# Carolo_31012020.net
KiCad netlist of a schematic drawn in EAGLE
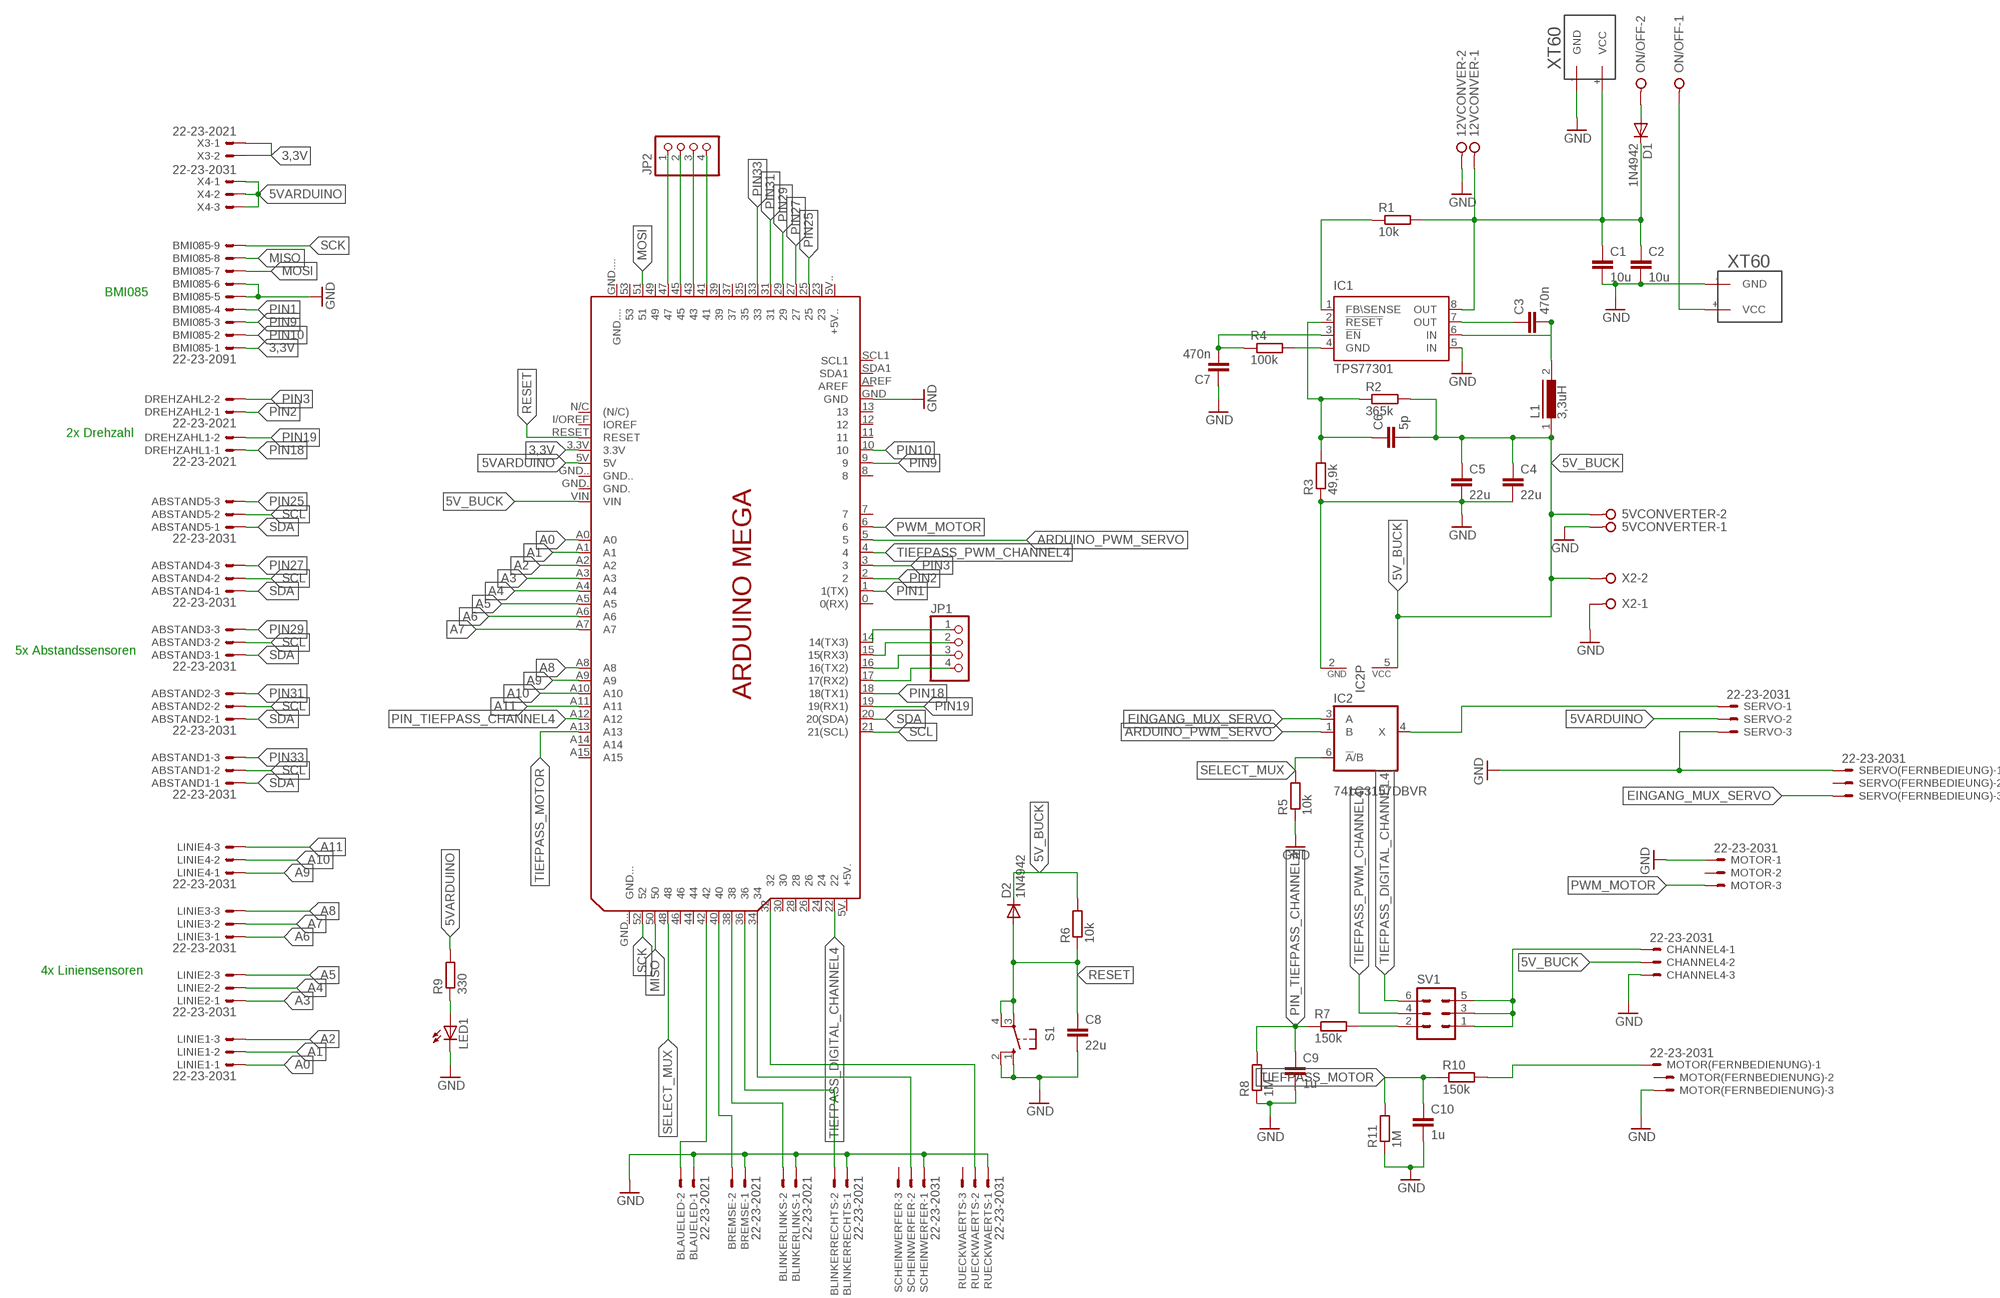
[diagram p0: schematic, sheet 1]

(export (version "E")
  (design (tool "Eeschema 10.0.6"))
  (components
    (comp (ref "5VCONVERTER")
      (value "W237-02P")
      (footprint "eagle-import:W237-132")
      (libsource (lib "eagle-import") (part "W237-02P"))
    )
    (comp (ref "12VCONVER")
      (value "W237-02P")
      (footprint "eagle-import:W237-132")
      (libsource (lib "eagle-import") (part "W237-02P"))
    )
    (comp (ref "ABSTAND1")
      (value "22-23-2031")
      (footprint "eagle-import:22-23-2031")
      (fields (field (name "MF") "MOLEX"))
      (libsource (lib "eagle-import") (part "22-23-2031"))
    )
    (comp (ref "ABSTAND2")
      (value "22-23-2031")
      (footprint "eagle-import:22-23-2031")
      (fields (field (name "MF") "MOLEX"))
      (libsource (lib "eagle-import") (part "22-23-2031"))
    )
    (comp (ref "ABSTAND3")
      (value "22-23-2031")
      (footprint "eagle-import:22-23-2031")
      (fields (field (name "MF") "MOLEX"))
      (libsource (lib "eagle-import") (part "22-23-2031"))
    )
    (comp (ref "ABSTAND4")
      (value "22-23-2031")
      (footprint "eagle-import:22-23-2031")
      (fields (field (name "MF") "MOLEX"))
      (libsource (lib "eagle-import") (part "22-23-2031"))
    )
    (comp (ref "ABSTAND5")
      (value "22-23-2031")
      (footprint "eagle-import:22-23-2031")
      (fields (field (name "MF") "MOLEX"))
      (libsource (lib "eagle-import") (part "22-23-2031"))
    )
    (comp (ref "BLAUELED")
      (value "22-23-2021")
      (footprint "eagle-import:22-23-2021")
      (fields (field (name "MF") "MOLEX"))
      (libsource (lib "eagle-import") (part "22-23-2021"))
    )
    (comp (ref "BLINKERLINKS")
      (value "22-23-2021")
      (footprint "eagle-import:22-23-2021")
      (fields (field (name "MF") "MOLEX"))
      (libsource (lib "eagle-import") (part "22-23-2021"))
    )
    (comp (ref "BLINKERRECHTS")
      (value "22-23-2021")
      (footprint "eagle-import:22-23-2021")
      (fields (field (name "MF") "MOLEX"))
      (libsource (lib "eagle-import") (part "22-23-2021"))
    )
    (comp (ref "BMI085")
      (value "22-23-2091")
      (footprint "eagle-import:22-23-2091")
      (fields (field (name "MF") "MOLEX"))
      (libsource (lib "eagle-import") (part "22-23-2091"))
    )
    (comp (ref "BREMSE")
      (value "22-23-2021")
      (footprint "eagle-import:22-23-2021")
      (fields (field (name "MF") "MOLEX"))
      (libsource (lib "eagle-import") (part "22-23-2021"))
    )
    (comp (ref "C1")
      (value "10u")
      (footprint "eagle-import:C2.5-3")
      (libsource (lib "eagle-import") (part "C2,5-3"))
    )
    (comp (ref "C2")
      (value "10u")
      (footprint "eagle-import:C2.5-3")
      (libsource (lib "eagle-import") (part "C2,5-3"))
    )
    (comp (ref "C3")
      (value "470n")
      (footprint "eagle-import:C2.5-3")
      (libsource (lib "eagle-import") (part "C2,5-3"))
    )
    (comp (ref "C4")
      (value "22u")
      (footprint "eagle-import:C2.5-3")
      (libsource (lib "eagle-import") (part "C2,5-3"))
    )
    (comp (ref "C5")
      (value "22u")
      (footprint "eagle-import:C2.5-3")
      (libsource (lib "eagle-import") (part "C2,5-3"))
    )
    (comp (ref "C6")
      (value "5p")
      (footprint "eagle-import:C2.5-3")
      (libsource (lib "eagle-import") (part "C2,5-3"))
    )
    (comp (ref "C7")
      (value "470n")
      (footprint "eagle-import:C2.5-3")
      (libsource (lib "eagle-import") (part "C2,5-3"))
    )
    (comp (ref "C8")
      (value "22u")
      (footprint "eagle-import:C2.5-3")
      (libsource (lib "eagle-import") (part "C2,5-3"))
    )
    (comp (ref "C9")
      (value "1u")
      (footprint "eagle-import:C2.5-3")
      (libsource (lib "eagle-import") (part "C2,5-3"))
    )
    (comp (ref "C10")
      (value "1u")
      (footprint "eagle-import:C2.5-3")
      (libsource (lib "eagle-import") (part "C2,5-3"))
    )
    (comp (ref "CHANNEL4")
      (value "22-23-2031")
      (footprint "eagle-import:22-23-2031")
      (fields (field (name "MF") "MOLEX"))
      (libsource (lib "eagle-import") (part "22-23-2031"))
    )
    (comp (ref "D1")
      (value "1N4942")
      (footprint "eagle-import:DO41-10")
      (libsource (lib "eagle-import") (part "1N4942"))
    )
    (comp (ref "D2")
      (value "1N4942")
      (footprint "eagle-import:DO41-10")
      (libsource (lib "eagle-import") (part "1N4942"))
    )
    (comp (ref "DREHZAHL1")
      (value "22-23-2021")
      (footprint "eagle-import:22-23-2021")
      (fields (field (name "MF") "MOLEX"))
      (libsource (lib "eagle-import") (part "22-23-2021"))
    )
    (comp (ref "DREHZAHL2")
      (value "22-23-2021")
      (footprint "eagle-import:22-23-2021")
      (fields (field (name "MF") "MOLEX"))
      (libsource (lib "eagle-import") (part "22-23-2021"))
    )
    (comp (ref "IC1")
      (value "TPS77301")
      (footprint "eagle-import:SOP-08")
      (fields (field (name "MF") "TEXAS INSTRUMENT CONNECTORS") (field (name "MPN") "TPS77301DGK"))
      (libsource (lib "eagle-import") (part "TPS77301"))
    )
    (comp (ref "IC2")
      (value "741G3157DBVR")
      (footprint "eagle-import:DBV_R-PDSO-G6")
      (libsource (lib "eagle-import") (part "741G3157DBVR"))
    )
    (comp (ref "JP1")
      (value "PINHD-1X4")
      (footprint "eagle-import:1X04")
      (libsource (lib "eagle-import") (part "PINHD-1X4"))
    )
    (comp (ref "JP2")
      (value "PINHD-1X4")
      (footprint "eagle-import:1X04")
      (libsource (lib "eagle-import") (part "PINHD-1X4"))
    )
    (comp (ref "L1")
      (value "3,3uH")
      (footprint "eagle-import:82114R")
      (libsource (lib "eagle-import") (part "82114R"))
    )
    (comp (ref "LED1")
      (value "LED5MM")
      (footprint "eagle-import:LED5MM")
      (libsource (lib "eagle-import") (part "LED5MM"))
    )
    (comp (ref "LINIE1")
      (value "22-23-2031")
      (footprint "eagle-import:22-23-2031")
      (fields (field (name "MF") "MOLEX"))
      (libsource (lib "eagle-import") (part "22-23-2031"))
    )
    (comp (ref "LINIE2")
      (value "22-23-2031")
      (footprint "eagle-import:22-23-2031")
      (fields (field (name "MF") "MOLEX"))
      (libsource (lib "eagle-import") (part "22-23-2031"))
    )
    (comp (ref "LINIE3")
      (value "22-23-2031")
      (footprint "eagle-import:22-23-2031")
      (fields (field (name "MF") "MOLEX"))
      (libsource (lib "eagle-import") (part "22-23-2031"))
    )
    (comp (ref "LINIE4")
      (value "22-23-2031")
      (footprint "eagle-import:22-23-2031")
      (fields (field (name "MF") "MOLEX"))
      (libsource (lib "eagle-import") (part "22-23-2031"))
    )
    (comp (ref "MOTOR")
      (value "22-23-2031")
      (footprint "eagle-import:22-23-2031")
      (fields (field (name "MF") "MOLEX"))
      (libsource (lib "eagle-import") (part "22-23-2031"))
    )
    (comp (ref "MOTOR(FERNBEDIENUNG)")
      (value "22-23-2031")
      (footprint "eagle-import:22-23-2031")
      (fields (field (name "MF") "MOLEX"))
      (libsource (lib "eagle-import") (part "22-23-2031"))
    )
    (comp (ref "ON/OFF")
      (value "W237-02P")
      (footprint "eagle-import:W237-132")
      (libsource (lib "eagle-import") (part "W237-02P"))
    )
    (comp (ref "PCB1")
      (value "ARDUINO_MEGA")
      (footprint "eagle-import:ARDUINO_MEGA")
      (libsource (lib "eagle-import") (part "ARDUINO_MEGA"))
    )
    (comp (ref "R1")
      (value "10k")
      (footprint "eagle-import:0411_15")
      (libsource (lib "eagle-import") (part "R-EU_0411/15"))
    )
    (comp (ref "R2")
      (value "365k")
      (footprint "eagle-import:0411_15")
      (libsource (lib "eagle-import") (part "R-EU_0411/15"))
    )
    (comp (ref "R3")
      (value "49,9k")
      (footprint "eagle-import:0411_15")
      (libsource (lib "eagle-import") (part "R-EU_0411/15"))
    )
    (comp (ref "R4")
      (value "100k")
      (footprint "eagle-import:0411_15")
      (libsource (lib "eagle-import") (part "R-EU_0411/15"))
    )
    (comp (ref "R5")
      (value "10k")
      (footprint "eagle-import:0411_15")
      (libsource (lib "eagle-import") (part "R-EU_0411/15"))
    )
    (comp (ref "R6")
      (value "10k")
      (footprint "eagle-import:0411_15")
      (libsource (lib "eagle-import") (part "R-EU_0411/15"))
    )
    (comp (ref "R7")
      (value "150k")
      (footprint "eagle-import:0411_15")
      (libsource (lib "eagle-import") (part "R-EU_0411/15"))
    )
    (comp (ref "R8")
      (value "1M")
      (footprint "eagle-import:0411_15")
      (libsource (lib "eagle-import") (part "R-EU_0411/15"))
    )
    (comp (ref "R9")
      (value "330")
      (footprint "eagle-import:0411_15")
      (libsource (lib "eagle-import") (part "R-EU_0411/15"))
    )
    (comp (ref "R10")
      (value "150k")
      (footprint "eagle-import:0411_15")
      (libsource (lib "eagle-import") (part "R-EU_0411/15"))
    )
    (comp (ref "R11")
      (value "1M")
      (footprint "eagle-import:0411_15")
      (libsource (lib "eagle-import") (part "R-EU_0411/15"))
    )
    (comp (ref "RUECKWAERTS")
      (value "22-23-2031")
      (footprint "eagle-import:22-23-2031")
      (fields (field (name "MF") "MOLEX"))
      (libsource (lib "eagle-import") (part "22-23-2031"))
    )
    (comp (ref "S1")
      (value "10-XX")
      (footprint "eagle-import:B3F-10XX")
      (fields (field (name "MPN") "B3F-1000"))
      (libsource (lib "eagle-import") (part "10-XX"))
    )
    (comp (ref "SCHEINWERFER")
      (value "22-23-2031")
      (footprint "eagle-import:22-23-2031")
      (fields (field (name "MF") "MOLEX"))
      (libsource (lib "eagle-import") (part "22-23-2031"))
    )
    (comp (ref "SERVO")
      (value "22-23-2031")
      (footprint "eagle-import:22-23-2031")
      (fields (field (name "MF") "MOLEX"))
      (libsource (lib "eagle-import") (part "22-23-2031"))
    )
    (comp (ref "SERVO(FERNBEDIEUNG)")
      (value "22-23-2031")
      (footprint "eagle-import:22-23-2031")
      (fields (field (name "MF") "MOLEX"))
      (libsource (lib "eagle-import") (part "22-23-2031"))
    )
    (comp (ref "SV1")
      (value "ML6")
      (footprint "eagle-import:ML6")
      (libsource (lib "eagle-import") (part "ML6"))
    )
    (comp (ref "U$1")
      (value "XT60")
      (footprint "eagle-import:XT60")
      (libsource (lib "eagle-import") (part "XT60"))
    )
    (comp (ref "U$2")
      (value "XT60")
      (footprint "eagle-import:XT60")
      (libsource (lib "eagle-import") (part "XT60"))
    )
    (comp (ref "X2")
      (value "W237-02P")
      (footprint "eagle-import:W237-132")
      (libsource (lib "eagle-import") (part "W237-02P"))
    )
    (comp (ref "X3")
      (value "22-23-2021")
      (footprint "eagle-import:22-23-2021")
      (fields (field (name "MF") "MOLEX"))
      (libsource (lib "eagle-import") (part "22-23-2021"))
    )
    (comp (ref "X4")
      (value "22-23-2031")
      (footprint "eagle-import:22-23-2031")
      (fields (field (name "MF") "MOLEX"))
      (libsource (lib "eagle-import") (part "22-23-2031"))
    )
  )
  (nets
    (net (code "1") (name "3,3V") (class "Default")
      (node (ref "BMI085") (pin "1") (pinfunction "S_1") (pintype "passive"))
      (node (ref "PCB1") (pin "3.3V") (pinfunction "3.3V_3.3V") (pintype "bidirectional"))
      (node (ref "X3") (pin "1") (pinfunction "S_1") (pintype "passive"))
      (node (ref "X3") (pin "2") (pinfunction "S_2") (pintype "passive"))
    )
    (net (code "2") (name "5VARDUINO") (class "Default")
      (node (ref "PCB1") (pin "5V") (pinfunction "5V_5V") (pintype "bidirectional"))
      (node (ref "R9") (pin "2") (pinfunction "2_2") (pintype "passive"))
      (node (ref "SERVO") (pin "2") (pinfunction "S_2") (pintype "passive"))
      (node (ref "X4") (pin "1") (pinfunction "S_1") (pintype "passive"))
      (node (ref "X4") (pin "2") (pinfunction "S_2") (pintype "passive"))
      (node (ref "X4") (pin "3") (pinfunction "S_3") (pintype "passive"))
    )
    (net (code "3") (name "5V_BUCK") (class "Default")
      (node (ref "5VCONVERTER") (pin "2") (pinfunction "KL_2") (pintype "passive"))
      (node (ref "C4") (pin "1") (pinfunction "1_1") (pintype "passive"))
      (node (ref "C5") (pin "1") (pinfunction "1_1") (pintype "passive"))
      (node (ref "C6") (pin "2") (pinfunction "2_2") (pintype "passive"))
      (node (ref "CHANNEL4") (pin "2") (pinfunction "S_2") (pintype "passive"))
      (node (ref "D2") (pin "C") (pinfunction "C_C") (pintype "passive"))
      (node (ref "IC2") (pin "5") (pinfunction "VCC_5") (pintype "power_in"))
      (node (ref "L1") (pin "1") (pinfunction "1_1") (pintype "passive"))
      (node (ref "PCB1") (pin "VIN") (pinfunction "VIN_VIN") (pintype "bidirectional"))
      (node (ref "R2") (pin "2") (pinfunction "2_2") (pintype "passive"))
      (node (ref "R6") (pin "2") (pinfunction "2_2") (pintype "passive"))
      (node (ref "X2") (pin "2") (pinfunction "KL_2") (pintype "passive"))
    )
    (net (code "4") (name "A0") (class "Default")
      (node (ref "LINIE1") (pin "1") (pinfunction "S_1") (pintype "passive"))
      (node (ref "PCB1") (pin "A0") (pinfunction "A0_A0") (pintype "bidirectional"))
    )
    (net (code "5") (name "A1") (class "Default")
      (node (ref "LINIE1") (pin "2") (pinfunction "S_2") (pintype "passive"))
      (node (ref "PCB1") (pin "A1") (pinfunction "A1_A1") (pintype "bidirectional"))
    )
    (net (code "6") (name "A2") (class "Default")
      (node (ref "LINIE1") (pin "3") (pinfunction "S_3") (pintype "passive"))
      (node (ref "PCB1") (pin "A2") (pinfunction "A2_A2") (pintype "bidirectional"))
    )
    (net (code "7") (name "A3") (class "Default")
      (node (ref "LINIE2") (pin "1") (pinfunction "S_1") (pintype "passive"))
      (node (ref "PCB1") (pin "A3") (pinfunction "A3_A3") (pintype "bidirectional"))
    )
    (net (code "8") (name "A4") (class "Default")
      (node (ref "LINIE2") (pin "2") (pinfunction "S_2") (pintype "passive"))
      (node (ref "PCB1") (pin "A4") (pinfunction "A4_A4") (pintype "bidirectional"))
    )
    (net (code "9") (name "A5") (class "Default")
      (node (ref "LINIE2") (pin "3") (pinfunction "S_3") (pintype "passive"))
      (node (ref "PCB1") (pin "A5") (pinfunction "A5_A5") (pintype "bidirectional"))
    )
    (net (code "10") (name "A6") (class "Default")
      (node (ref "LINIE3") (pin "1") (pinfunction "S_1") (pintype "passive"))
      (node (ref "PCB1") (pin "A6") (pinfunction "A6_A6") (pintype "bidirectional"))
    )
    (net (code "11") (name "A7") (class "Default")
      (node (ref "LINIE3") (pin "2") (pinfunction "S_2") (pintype "passive"))
      (node (ref "PCB1") (pin "A7") (pinfunction "A7_A7") (pintype "bidirectional"))
    )
    (net (code "12") (name "A8") (class "Default")
      (node (ref "LINIE3") (pin "3") (pinfunction "S_3") (pintype "passive"))
      (node (ref "PCB1") (pin "A8") (pinfunction "A8_A8") (pintype "bidirectional"))
    )
    (net (code "13") (name "A9") (class "Default")
      (node (ref "LINIE4") (pin "1") (pinfunction "S_1") (pintype "passive"))
      (node (ref "PCB1") (pin "A9") (pinfunction "A9_A9") (pintype "bidirectional"))
    )
    (net (code "14") (name "A10") (class "Default")
      (node (ref "LINIE4") (pin "2") (pinfunction "S_2") (pintype "passive"))
      (node (ref "PCB1") (pin "A10") (pinfunction "A10_A10") (pintype "bidirectional"))
    )
    (net (code "15") (name "A11") (class "Default")
      (node (ref "LINIE4") (pin "3") (pinfunction "S_3") (pintype "passive"))
      (node (ref "PCB1") (pin "A11") (pinfunction "A11_A11") (pintype "bidirectional"))
    )
    (net (code "16") (name "ARDUINO_PWM_SERVO") (class "Default")
      (node (ref "IC2") (pin "1") (pinfunction "B_1") (pintype "bidirectional"))
      (node (ref "PCB1") (pin "5") (pinfunction "5_5") (pintype "bidirectional"))
    )
    (net (code "17") (name "EINGANG_MUX_SERVO") (class "Default")
      (node (ref "IC2") (pin "3") (pinfunction "A_3") (pintype "bidirectional"))
      (node (ref "SERVO(FERNBEDIEUNG)") (pin "3") (pinfunction "S_3") (pintype "passive"))
    )
    (net (code "18") (name "GND") (class "Default")
      (node (ref "12VCONVER") (pin "2") (pinfunction "KL_2") (pintype "passive"))
      (node (ref "5VCONVERTER") (pin "1") (pinfunction "KL_1") (pintype "passive"))
      (node (ref "BLAUELED") (pin "1") (pinfunction "S_1") (pintype "passive"))
      (node (ref "BLINKERLINKS") (pin "1") (pinfunction "S_1") (pintype "passive"))
      (node (ref "BLINKERRECHTS") (pin "1") (pinfunction "S_1") (pintype "passive"))
      (node (ref "BMI085") (pin "5") (pinfunction "S_5") (pintype "passive"))
      (node (ref "BMI085") (pin "6") (pinfunction "S_6") (pintype "passive"))
      (node (ref "BREMSE") (pin "1") (pinfunction "S_1") (pintype "passive"))
      (node (ref "C1") (pin "2") (pinfunction "2_2") (pintype "passive"))
      (node (ref "C10") (pin "2") (pinfunction "2_2") (pintype "passive"))
      (node (ref "C2") (pin "2") (pinfunction "2_2") (pintype "passive"))
      (node (ref "C4") (pin "2") (pinfunction "2_2") (pintype "passive"))
      (node (ref "C5") (pin "2") (pinfunction "2_2") (pintype "passive"))
      (node (ref "C7") (pin "1") (pinfunction "1_1") (pintype "passive"))
      (node (ref "C8") (pin "2") (pinfunction "2_2") (pintype "passive"))
      (node (ref "C9") (pin "2") (pinfunction "2_2") (pintype "passive"))
      (node (ref "CHANNEL4") (pin "3") (pinfunction "S_3") (pintype "passive"))
      (node (ref "IC1") (pin "5") (pinfunction "IN_5") (pintype "input"))
      (node (ref "IC2") (pin "2") (pinfunction "GND_2") (pintype "power_in"))
      (node (ref "LED1") (pin "K") (pinfunction "C_K") (pintype "passive"))
      (node (ref "MOTOR") (pin "1") (pinfunction "S_1") (pintype "passive"))
      (node (ref "MOTOR(FERNBEDIENUNG)") (pin "3") (pinfunction "S_3") (pintype "passive"))
      (node (ref "PCB1") (pin "GND") (pinfunction "GND_GND") (pintype "bidirectional"))
      (node (ref "R11") (pin "1") (pinfunction "1_1") (pintype "passive"))
      (node (ref "R3") (pin "1") (pinfunction "1_1") (pintype "passive"))
      (node (ref "R5") (pin "1") (pinfunction "1_1") (pintype "passive"))
      (node (ref "R8") (pin "1") (pinfunction "1_1") (pintype "passive"))
      (node (ref "RUECKWAERTS") (pin "1") (pinfunction "S_1") (pintype "passive"))
      (node (ref "S1") (pin "1") (pinfunction "S_1") (pintype "passive"))
      (node (ref "S1") (pin "2") (pinfunction "S1_2") (pintype "passive"))
      (node (ref "SCHEINWERFER") (pin "1") (pinfunction "S_1") (pintype "passive"))
      (node (ref "SERVO") (pin "3") (pinfunction "S_3") (pintype "passive"))
      (node (ref "SERVO(FERNBEDIEUNG)") (pin "1") (pinfunction "S_1") (pintype "passive"))
      (node (ref "U$1") (pin "-") (pinfunction "GND_-") (pintype "bidirectional"))
      (node (ref "U$2") (pin "-") (pinfunction "GND_-") (pintype "bidirectional"))
      (node (ref "X2") (pin "1") (pinfunction "KL_1") (pintype "passive"))
    )
    (net (code "19") (name "MISO") (class "Default")
      (node (ref "BMI085") (pin "8") (pinfunction "S_8") (pintype "passive"))
      (node (ref "PCB1") (pin "50") (pinfunction "50_50") (pintype "bidirectional"))
    )
    (net (code "20") (name "MOSI") (class "Default")
      (node (ref "BMI085") (pin "7") (pinfunction "S_7") (pintype "passive"))
      (node (ref "PCB1") (pin "51") (pinfunction "51_51") (pintype "bidirectional"))
    )
    (net (code "21") (name "Net-(12VCONVERA-KL)") (class "Default")
      (node (ref "12VCONVER") (pin "1") (pinfunction "KL_1") (pintype "passive"))
      (node (ref "C1") (pin "1") (pinfunction "1_1") (pintype "passive"))
      (node (ref "C2") (pin "1") (pinfunction "1_1") (pintype "passive"))
      (node (ref "D1") (pin "C") (pinfunction "C_C") (pintype "passive"))
      (node (ref "IC1") (pin "8") (pinfunction "OUT_8") (pintype "passive"))
      (node (ref "R1") (pin "2") (pinfunction "2_2") (pintype "passive"))
      (node (ref "U$2") (pin "+") (pinfunction "VCC_+") (pintype "bidirectional"))
    )
    (net (code "22") (name "Net-(BLAUELEDB-S)") (class "Default")
      (node (ref "BLAUELED") (pin "2") (pinfunction "S_2") (pintype "passive"))
      (node (ref "PCB1") (pin "42") (pinfunction "42_42") (pintype "bidirectional"))
    )
    (net (code "23") (name "Net-(BLINKERLINKSB-S)") (class "Default")
      (node (ref "BLINKERLINKS") (pin "2") (pinfunction "S_2") (pintype "passive"))
      (node (ref "PCB1") (pin "38") (pinfunction "38_38") (pintype "bidirectional"))
    )
    (net (code "24") (name "Net-(BLINKERRECHTSB-S)") (class "Default")
      (node (ref "BLINKERRECHTS") (pin "2") (pinfunction "S_2") (pintype "passive"))
      (node (ref "PCB1") (pin "36") (pinfunction "36_36") (pintype "bidirectional"))
    )
    (net (code "25") (name "Net-(BREMSEB-S)") (class "Default")
      (node (ref "BREMSE") (pin "2") (pinfunction "S_2") (pintype "passive"))
      (node (ref "PCB1") (pin "40") (pinfunction "40_40") (pintype "bidirectional"))
    )
    (net (code "26") (name "Net-(C3-Pad1)") (class "Default")
      (node (ref "C3") (pin "1") (pinfunction "1_1") (pintype "passive"))
      (node (ref "IC1") (pin "7") (pinfunction "OUT_7") (pintype "output"))
    )
    (net (code "27") (name "Net-(C3-Pad2)") (class "Default")
      (node (ref "C3") (pin "2") (pinfunction "2_2") (pintype "passive"))
      (node (ref "IC1") (pin "6") (pinfunction "IN_6") (pintype "input"))
      (node (ref "L1") (pin "2") (pinfunction "2_2") (pintype "passive"))
    )
    (net (code "28") (name "Net-(CHANNEL4A-S)") (class "Default")
      (node (ref "CHANNEL4") (pin "1") (pinfunction "S_1") (pintype "passive"))
      (node (ref "SV1") (pin "1") (pinfunction "1_1") (pintype "passive"))
      (node (ref "SV1") (pin "3") (pinfunction "3_3") (pintype "passive"))
      (node (ref "SV1") (pin "5") (pinfunction "5_5") (pintype "passive"))
    )
    (net (code "29") (name "Net-(IC1-FB\\SENSE)") (class "Default")
      (node (ref "IC1") (pin "1") (pinfunction "FB\\SENSE_1") (pintype "input"))
      (node (ref "R1") (pin "1") (pinfunction "1_1") (pintype "passive"))
    )
    (net (code "30") (name "Net-(IC1-GND)") (class "Default")
      (node (ref "IC1") (pin "4") (pinfunction "GND_4") (pintype "power_in"))
      (node (ref "R4") (pin "2") (pinfunction "2_2") (pintype "passive"))
    )
    (net (code "31") (name "Net-(IC1-~{EN})") (class "Default")
      (node (ref "C7") (pin "2") (pinfunction "2_2") (pintype "passive"))
      (node (ref "IC1") (pin "3") (pinfunction "~{EN}_3") (pintype "input"))
      (node (ref "R4") (pin "1") (pinfunction "1_1") (pintype "passive"))
    )
    (net (code "32") (name "Net-(IC1-~{RESET})") (class "Default")
      (node (ref "C6") (pin "1") (pinfunction "1_1") (pintype "passive"))
      (node (ref "IC1") (pin "2") (pinfunction "~{RESET}_2") (pintype "input"))
      (node (ref "R2") (pin "1") (pinfunction "1_1") (pintype "passive"))
      (node (ref "R3") (pin "2") (pinfunction "2_2") (pintype "passive"))
    )
    (net (code "33") (name "Net-(IC2A-X)") (class "Default")
      (node (ref "IC2") (pin "4") (pinfunction "X_4") (pintype "bidirectional"))
      (node (ref "SERVO") (pin "1") (pinfunction "S_1") (pintype "passive"))
    )
    (net (code "34") (name "Net-(JP2-Pad1)") (class "Default")
      (node (ref "JP2") (pin "1") (pinfunction "1_1") (pintype "passive"))
      (node (ref "PCB1") (pin "47") (pinfunction "47_47") (pintype "bidirectional"))
    )
    (net (code "35") (name "Net-(JP2-Pad2)") (class "Default")
      (node (ref "JP2") (pin "2") (pinfunction "2_2") (pintype "passive"))
      (node (ref "PCB1") (pin "45") (pinfunction "45_45") (pintype "bidirectional"))
    )
    (net (code "36") (name "Net-(JP2-Pad3)") (class "Default")
      (node (ref "JP2") (pin "3") (pinfunction "3_3") (pintype "passive"))
      (node (ref "PCB1") (pin "43") (pinfunction "43_43") (pintype "bidirectional"))
    )
    (net (code "37") (name "Net-(JP2-Pad4)") (class "Default")
      (node (ref "JP2") (pin "4") (pinfunction "4_4") (pintype "passive"))
      (node (ref "PCB1") (pin "41") (pinfunction "41_41") (pintype "bidirectional"))
    )
    (net (code "38") (name "Net-(LED1-PadA)") (class "Default")
      (node (ref "LED1") (pin "A") (pinfunction "A_A") (pintype "passive"))
      (node (ref "R9") (pin "1") (pinfunction "1_1") (pintype "passive"))
    )
    (net (code "39") (name "Net-(MOTOR(FERNBEDIENUNG)A-S)") (class "Default")
      (node (ref "MOTOR(FERNBEDIENUNG)") (pin "1") (pinfunction "S_1") (pintype "passive"))
      (node (ref "R10") (pin "2") (pinfunction "2_2") (pintype "passive"))
    )
    (net (code "40") (name "Net-(ON/OFFA-KL)") (class "Default")
      (node (ref "ON/OFF") (pin "1") (pinfunction "KL_1") (pintype "passive"))
      (node (ref "U$1") (pin "+") (pinfunction "VCC_+") (pintype "bidirectional"))
    )
    (net (code "41") (name "Net-(ON/OFFB-KL)") (class "Default")
      (node (ref "D1") (pin "A") (pinfunction "A_A") (pintype "passive"))
      (node (ref "ON/OFF") (pin "2") (pinfunction "KL_2") (pintype "passive"))
    )
    (net (code "42") (name "Net-(PCB1-14(TX3))") (class "Default")
      (node (ref "JP1") (pin "1") (pinfunction "1_1") (pintype "passive"))
      (node (ref "PCB1") (pin "14") (pinfunction "14(TX3)_14") (pintype "bidirectional"))
    )
    (net (code "43") (name "Net-(PCB1-15(RX3))") (class "Default")
      (node (ref "JP1") (pin "2") (pinfunction "2_2") (pintype "passive"))
      (node (ref "PCB1") (pin "15") (pinfunction "15(RX3)_15") (pintype "bidirectional"))
    )
    (net (code "44") (name "Net-(PCB1-16(TX2))") (class "Default")
      (node (ref "JP1") (pin "3") (pinfunction "3_3") (pintype "passive"))
      (node (ref "PCB1") (pin "16") (pinfunction "16(TX2)_16") (pintype "bidirectional"))
    )
    (net (code "45") (name "Net-(PCB1-17(RX2))") (class "Default")
      (node (ref "JP1") (pin "4") (pinfunction "4_4") (pintype "passive"))
      (node (ref "PCB1") (pin "17") (pinfunction "17(RX2)_17") (pintype "bidirectional"))
    )
    (net (code "46") (name "Net-(R7-Pad2)") (class "Default")
      (node (ref "R7") (pin "2") (pinfunction "2_2") (pintype "passive"))
      (node (ref "SV1") (pin "2") (pinfunction "2_2") (pintype "passive"))
    )
    (net (code "47") (name "Net-(RUECKWAERTSB-S)") (class "Default")
      (node (ref "PCB1") (pin "32") (pinfunction "32_32") (pintype "bidirectional"))
      (node (ref "RUECKWAERTS") (pin "2") (pinfunction "S_2") (pintype "passive"))
    )
    (net (code "48") (name "Net-(SCHEINWERFERB-S)") (class "Default")
      (node (ref "PCB1") (pin "34") (pinfunction "34_34") (pintype "bidirectional"))
      (node (ref "SCHEINWERFER") (pin "2") (pinfunction "S_2") (pintype "passive"))
    )
    (net (code "49") (name "PIN1") (class "Default")
      (node (ref "BMI085") (pin "4") (pinfunction "S_4") (pintype "passive"))
      (node (ref "PCB1") (pin "1") (pinfunction "1(TX)_1") (pintype "bidirectional"))
    )
    (net (code "50") (name "PIN2") (class "Default")
      (node (ref "DREHZAHL2") (pin "1") (pinfunction "S_1") (pintype "passive"))
      (node (ref "PCB1") (pin "2") (pinfunction "2_2") (pintype "bidirectional"))
    )
    (net (code "51") (name "PIN3") (class "Default")
      (node (ref "DREHZAHL2") (pin "2") (pinfunction "S_2") (pintype "passive"))
      (node (ref "PCB1") (pin "3") (pinfunction "3_3") (pintype "bidirectional"))
    )
    (net (code "52") (name "PIN9") (class "Default")
      (node (ref "BMI085") (pin "3") (pinfunction "S_3") (pintype "passive"))
      (node (ref "PCB1") (pin "9") (pinfunction "9_9") (pintype "bidirectional"))
    )
    (net (code "53") (name "PIN10") (class "Default")
      (node (ref "BMI085") (pin "2") (pinfunction "S_2") (pintype "passive"))
      (node (ref "PCB1") (pin "10") (pinfunction "10_10") (pintype "bidirectional"))
    )
    (net (code "54") (name "PIN18") (class "Default")
      (node (ref "DREHZAHL1") (pin "1") (pinfunction "S_1") (pintype "passive"))
      (node (ref "PCB1") (pin "18") (pinfunction "18(TX1)_18") (pintype "bidirectional"))
    )
    (net (code "55") (name "PIN19") (class "Default")
      (node (ref "DREHZAHL1") (pin "2") (pinfunction "S_2") (pintype "passive"))
      (node (ref "PCB1") (pin "19") (pinfunction "19(RX1)_19") (pintype "bidirectional"))
    )
    (net (code "56") (name "PIN25") (class "Default")
      (node (ref "ABSTAND5") (pin "3") (pinfunction "S_3") (pintype "passive"))
      (node (ref "PCB1") (pin "25") (pinfunction "25_25") (pintype "bidirectional"))
    )
    (net (code "57") (name "PIN27") (class "Default")
      (node (ref "ABSTAND4") (pin "3") (pinfunction "S_3") (pintype "passive"))
      (node (ref "PCB1") (pin "27") (pinfunction "27_27") (pintype "bidirectional"))
    )
    (net (code "58") (name "PIN29") (class "Default")
      (node (ref "ABSTAND3") (pin "3") (pinfunction "S_3") (pintype "passive"))
      (node (ref "PCB1") (pin "29") (pinfunction "29_29") (pintype "bidirectional"))
    )
    (net (code "59") (name "PIN31") (class "Default")
      (node (ref "ABSTAND2") (pin "3") (pinfunction "S_3") (pintype "passive"))
      (node (ref "PCB1") (pin "31") (pinfunction "31_31") (pintype "bidirectional"))
    )
    (net (code "60") (name "PIN33") (class "Default")
      (node (ref "ABSTAND1") (pin "3") (pinfunction "S_3") (pintype "passive"))
      (node (ref "PCB1") (pin "33") (pinfunction "33_33") (pintype "bidirectional"))
    )
    (net (code "61") (name "PIN_TIEFPASS_CHANNEL4") (class "Default")
      (node (ref "C9") (pin "1") (pinfunction "1_1") (pintype "passive"))
      (node (ref "PCB1") (pin "A12") (pinfunction "A12_A12") (pintype "bidirectional"))
      (node (ref "R7") (pin "1") (pinfunction "1_1") (pintype "passive"))
      (node (ref "R8") (pin "2") (pinfunction "2_2") (pintype "passive"))
    )
    (net (code "62") (name "PWM_MOTOR") (class "Default")
      (node (ref "MOTOR") (pin "3") (pinfunction "S_3") (pintype "passive"))
      (node (ref "PCB1") (pin "6") (pinfunction "6_6") (pintype "bidirectional"))
    )
    (net (code "63") (name "RESET") (class "Default")
      (node (ref "C8") (pin "1") (pinfunction "1_1") (pintype "passive"))
      (node (ref "D2") (pin "A") (pinfunction "A_A") (pintype "passive"))
      (node (ref "PCB1") (pin "RESET") (pinfunction "RESET_RESET") (pintype "bidirectional"))
      (node (ref "R6") (pin "1") (pinfunction "1_1") (pintype "passive"))
      (node (ref "S1") (pin "3") (pinfunction "P_3") (pintype "passive"))
      (node (ref "S1") (pin "4") (pinfunction "P1_4") (pintype "passive"))
    )
    (net (code "64") (name "SCK") (class "Default")
      (node (ref "BMI085") (pin "9") (pinfunction "S_9") (pintype "passive"))
      (node (ref "PCB1") (pin "52") (pinfunction "52_52") (pintype "bidirectional"))
    )
    (net (code "65") (name "SCL") (class "Default")
      (node (ref "ABSTAND1") (pin "2") (pinfunction "S_2") (pintype "passive"))
      (node (ref "ABSTAND2") (pin "2") (pinfunction "S_2") (pintype "passive"))
      (node (ref "ABSTAND3") (pin "2") (pinfunction "S_2") (pintype "passive"))
      (node (ref "ABSTAND4") (pin "2") (pinfunction "S_2") (pintype "passive"))
      (node (ref "ABSTAND5") (pin "2") (pinfunction "S_2") (pintype "passive"))
      (node (ref "PCB1") (pin "21") (pinfunction "21(SCL)_21") (pintype "bidirectional"))
    )
    (net (code "66") (name "SDA") (class "Default")
      (node (ref "ABSTAND1") (pin "1") (pinfunction "S_1") (pintype "passive"))
      (node (ref "ABSTAND2") (pin "1") (pinfunction "S_1") (pintype "passive"))
      (node (ref "ABSTAND3") (pin "1") (pinfunction "S_1") (pintype "passive"))
      (node (ref "ABSTAND4") (pin "1") (pinfunction "S_1") (pintype "passive"))
      (node (ref "ABSTAND5") (pin "1") (pinfunction "S_1") (pintype "passive"))
      (node (ref "PCB1") (pin "20") (pinfunction "20(SDA)_20") (pintype "bidirectional"))
    )
    (net (code "67") (name "SELECT_MUX") (class "Default")
      (node (ref "IC2") (pin "6") (pinfunction "~{A}/B_6") (pintype "input"))
      (node (ref "PCB1") (pin "48") (pinfunction "48_48") (pintype "bidirectional"))
      (node (ref "R5") (pin "2") (pinfunction "2_2") (pintype "passive"))
    )
    (net (code "68") (name "TIEFPASS_DIGITAL_CHANNEL4") (class "Default")
      (node (ref "PCB1") (pin "22") (pinfunction "22_22") (pintype "bidirectional"))
      (node (ref "SV1") (pin "6") (pinfunction "6_6") (pintype "passive"))
    )
    (net (code "69") (name "TIEFPASS_MOTOR") (class "Default")
      (node (ref "C10") (pin "1") (pinfunction "1_1") (pintype "passive"))
      (node (ref "PCB1") (pin "A13") (pinfunction "A13_A13") (pintype "bidirectional"))
      (node (ref "R10") (pin "1") (pinfunction "1_1") (pintype "passive"))
      (node (ref "R11") (pin "2") (pinfunction "2_2") (pintype "passive"))
    )
    (net (code "70") (name "TIEFPASS_PWM_CHANNEL4") (class "Default")
      (node (ref "PCB1") (pin "4") (pinfunction "4_4") (pintype "bidirectional"))
      (node (ref "SV1") (pin "4") (pinfunction "4_4") (pintype "passive"))
    )
    (net (code "71") (name "unconnected-(MOTOR(FERNBEDIENUNG)B-S-Pad2)") (class "Default")
      (node (ref "MOTOR(FERNBEDIENUNG)") (pin "2") (pinfunction "S_2") (pintype "passive"))
    )
    (net (code "72") (name "unconnected-(MOTORB-S-Pad2)") (class "Default")
      (node (ref "MOTOR") (pin "2") (pinfunction "S_2") (pintype "passive"))
    )
    (net (code "73") (name "unconnected-(PCB1-(N{slash}C)-PadN{slash}C)") (class "Default")
      (node (ref "PCB1") (pin "N/C") (pinfunction "(N/C)_N/C") (pintype "bidirectional"))
    )
    (net (code "74") (name "unconnected-(PCB1-+5V.-Pad5V.)") (class "Default")
      (node (ref "PCB1") (pin "5V.") (pinfunction "+5V._5V.") (pintype "bidirectional"))
    )
    (net (code "75") (name "unconnected-(PCB1-+5V..-Pad5V..)") (class "Default")
      (node (ref "PCB1") (pin "5V..") (pinfunction "+5V.._5V..") (pintype "bidirectional"))
    )
    (net (code "76") (name "unconnected-(PCB1-0(RX)-Pad0)") (class "Default")
      (node (ref "PCB1") (pin "0") (pinfunction "0(RX)_0") (pintype "bidirectional"))
    )
    (net (code "77") (name "unconnected-(PCB1-IOREF-PadI{slash}OREF)") (class "Default")
      (node (ref "PCB1") (pin "I/OREF") (pinfunction "IOREF_I/OREF") (pintype "bidirectional"))
    )
    (net (code "78") (name "unconnected-(PCB1-Pad7)") (class "Default")
      (node (ref "PCB1") (pin "7") (pinfunction "7_7") (pintype "bidirectional"))
    )
    (net (code "79") (name "unconnected-(PCB1-Pad8)") (class "Default")
      (node (ref "PCB1") (pin "8") (pinfunction "8_8") (pintype "bidirectional"))
    )
    (net (code "80") (name "unconnected-(PCB1-Pad11)") (class "Default")
      (node (ref "PCB1") (pin "11") (pinfunction "11_11") (pintype "bidirectional"))
    )
    (net (code "81") (name "unconnected-(PCB1-Pad12)") (class "Default")
      (node (ref "PCB1") (pin "12") (pinfunction "12_12") (pintype "bidirectional"))
    )
    (net (code "82") (name "unconnected-(PCB1-Pad13)") (class "Default")
      (node (ref "PCB1") (pin "13") (pinfunction "13_13") (pintype "bidirectional"))
    )
    (net (code "83") (name "unconnected-(PCB1-Pad23)") (class "Default")
      (node (ref "PCB1") (pin "23") (pinfunction "23_23") (pintype "bidirectional"))
    )
    (net (code "84") (name "unconnected-(PCB1-Pad24)") (class "Default")
      (node (ref "PCB1") (pin "24") (pinfunction "24_24") (pintype "bidirectional"))
    )
    (net (code "85") (name "unconnected-(PCB1-Pad26)") (class "Default")
      (node (ref "PCB1") (pin "26") (pinfunction "26_26") (pintype "bidirectional"))
    )
    (net (code "86") (name "unconnected-(PCB1-Pad28)") (class "Default")
      (node (ref "PCB1") (pin "28") (pinfunction "28_28") (pintype "bidirectional"))
    )
    (net (code "87") (name "unconnected-(PCB1-Pad30)") (class "Default")
      (node (ref "PCB1") (pin "30") (pinfunction "30_30") (pintype "bidirectional"))
    )
    (net (code "88") (name "unconnected-(PCB1-Pad35)") (class "Default")
      (node (ref "PCB1") (pin "35") (pinfunction "35_35") (pintype "bidirectional"))
    )
    (net (code "89") (name "unconnected-(PCB1-Pad37)") (class "Default")
      (node (ref "PCB1") (pin "37") (pinfunction "37_37") (pintype "bidirectional"))
    )
    (net (code "90") (name "unconnected-(PCB1-Pad39)") (class "Default")
      (node (ref "PCB1") (pin "39") (pinfunction "39_39") (pintype "bidirectional"))
    )
    (net (code "91") (name "unconnected-(PCB1-Pad44)") (class "Default")
      (node (ref "PCB1") (pin "44") (pinfunction "44_44") (pintype "bidirectional"))
    )
    (net (code "92") (name "unconnected-(PCB1-Pad46)") (class "Default")
      (node (ref "PCB1") (pin "46") (pinfunction "46_46") (pintype "bidirectional"))
    )
    (net (code "93") (name "unconnected-(PCB1-Pad49)") (class "Default")
      (node (ref "PCB1") (pin "49") (pinfunction "49_49") (pintype "bidirectional"))
    )
    (net (code "94") (name "unconnected-(PCB1-Pad53)") (class "Default")
      (node (ref "PCB1") (pin "53") (pinfunction "53_53") (pintype "bidirectional"))
    )
    (net (code "95") (name "unconnected-(PCB1-PadA14)") (class "Default")
      (node (ref "PCB1") (pin "A14") (pinfunction "A14_A14") (pintype "bidirectional"))
    )
    (net (code "96") (name "unconnected-(PCB1-PadA15)") (class "Default")
      (node (ref "PCB1") (pin "A15") (pinfunction "A15_A15") (pintype "bidirectional"))
    )
    (net (code "97") (name "unconnected-(PCB1-PadAREF)") (class "Default")
      (node (ref "PCB1") (pin "AREF") (pinfunction "AREF_AREF") (pintype "bidirectional"))
    )
    (net (code "98") (name "unconnected-(PCB1-PadGND.)") (class "Default")
      (node (ref "PCB1") (pin "GND.") (pinfunction "GND._GND.") (pintype "bidirectional"))
    )
    (net (code "99") (name "unconnected-(PCB1-PadGND..)") (class "Default")
      (node (ref "PCB1") (pin "GND..") (pinfunction "GND.._GND..") (pintype "bidirectional"))
    )
    (net (code "100") (name "unconnected-(PCB1-PadGND...)") (class "Default")
      (node (ref "PCB1") (pin "GND...") (pinfunction "GND..._GND...") (pintype "bidirectional"))
    )
    (net (code "101") (name "unconnected-(PCB1-PadGND....)") (class "Default")
      (node (ref "PCB1") (pin "GND....") (pinfunction "GND...._GND....") (pintype "bidirectional"))
    )
    (net (code "102") (name "unconnected-(PCB1-PadSCL1)") (class "Default")
      (node (ref "PCB1") (pin "SCL1") (pinfunction "SCL1_SCL1") (pintype "bidirectional"))
    )
    (net (code "103") (name "unconnected-(PCB1-PadSDA1)") (class "Default")
      (node (ref "PCB1") (pin "SDA1") (pinfunction "SDA1_SDA1") (pintype "bidirectional"))
    )
    (net (code "104") (name "unconnected-(RUECKWAERTSC-S-Pad3)") (class "Default")
      (node (ref "RUECKWAERTS") (pin "3") (pinfunction "S_3") (pintype "passive"))
    )
    (net (code "105") (name "unconnected-(SCHEINWERFERC-S-Pad3)") (class "Default")
      (node (ref "SCHEINWERFER") (pin "3") (pinfunction "S_3") (pintype "passive"))
    )
    (net (code "106") (name "unconnected-(SERVO(FERNBEDIEUNG)B-S-Pad2)") (class "Default")
      (node (ref "SERVO(FERNBEDIEUNG)") (pin "2") (pinfunction "S_2") (pintype "passive"))
    )
  )
)
